# ESP12_PCB.net
KiCad netlist of a schematic drawn in Altium Designer
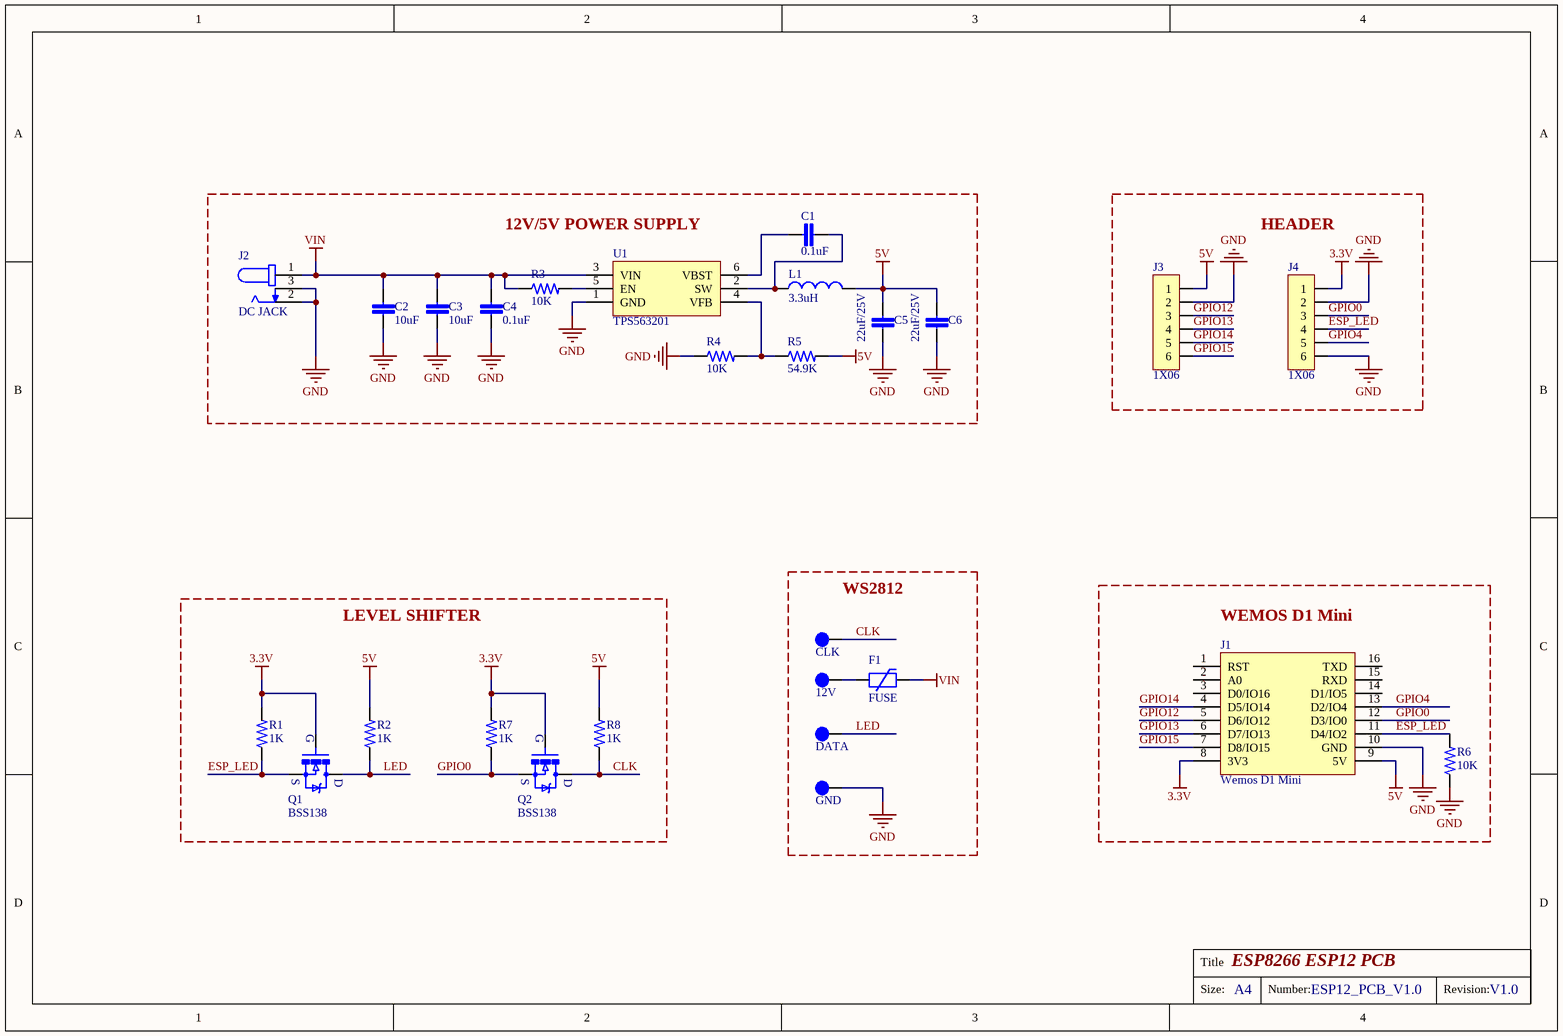
[diagram p0: ESP12_PCB.SchDoc]

(export (version "E")
  (design (tool "Eeschema 10.0.6"))
  (components
    (comp (ref "12V")
      (value "TestPoint")
      (footprint "TestPoint")
      (description "Test Point")
      (libsource (lib "Schematic_Library") (part "TestPoint"))
    )
    (comp (ref "C1")
      (value "0.1uF")
      (footprint "C1206")
      (description "0.1µF ±10% 50V Ceramic Capacitor X7R 1206 (3216 Metric)")
      (fields
        (field (name "MANUFACTURER") "Samsung")
        (field (name "MANUFACTURER PART NUMBER") "CL31B104KBCNFNC")
      )
      (libsource (lib "Schematic_Library") (part "C1206_0.1uF_50V"))
    )
    (comp (ref "C2")
      (value "10uF")
      (footprint "C1206")
      (description "10µF -20%, +80% 16V Ceramic Capacitor Y5V (F) 1206 (3216 Metric)")
      (fields
        (field (name "MANUFACTURER") "Samsung")
        (field (name "MANUFACTURER PART NUMBER") "CL31F106ZOHNNNE")
      )
      (libsource (lib "Schematic_Library") (part "C1206_10uF_16V"))
    )
    (comp (ref "C3")
      (value "10uF")
      (footprint "C1206")
      (description "10µF -20%, +80% 16V Ceramic Capacitor Y5V (F) 1206 (3216 Metric)")
      (fields
        (field (name "MANUFACTURER") "Samsung")
        (field (name "MANUFACTURER PART NUMBER") "CL31F106ZOHNNNE")
      )
      (libsource (lib "Schematic_Library") (part "C1206_10uF_16V"))
    )
    (comp (ref "C4")
      (value "0.1uF")
      (footprint "C1206")
      (description "0.1µF ±10% 50V Ceramic Capacitor X7R 1206 (3216 Metric)")
      (fields
        (field (name "MANUFACTURER") "Samsung")
        (field (name "MANUFACTURER PART NUMBER") "CL31B104KBCNFNC")
      )
      (libsource (lib "") (part "C1206_0.1uF_50V_1"))
    )
    (comp (ref "C5")
      (value "22uF/25V")
      (footprint "C1206")
      (description "Cap Ceramic 22uF 25V X5R 10% SMD 1206 85C Embossed T/R")
      (fields
        (field (name "MANUFACTURER") "Samsung")
        (field (name "MANUFACTURER PART NUMBER") "CL31A226KAHNNNE")
      )
      (libsource (lib "Schematic_Library") (part "C1206_22uF_25V"))
    )
    (comp (ref "C6")
      (value "22uF/25V")
      (footprint "C1206")
      (description "Cap Ceramic 22uF 25V X5R 10% SMD 1206 85C Embossed T/R")
      (fields
        (field (name "MANUFACTURER") "Samsung")
        (field (name "MANUFACTURER PART NUMBER") "CL31A226KAHNNNE")
      )
      (libsource (lib "Schematic_Library") (part "C1206_22uF_25V"))
    )
    (comp (ref "CLK")
      (value "TestPoint")
      (footprint "TestPoint")
      (description "Test Point")
      (libsource (lib "Schematic_Library") (part "TestPoint"))
    )
    (comp (ref "DATA")
      (value "TestPoint")
      (footprint "TestPoint")
      (description "Test Point")
      (libsource (lib "Schematic_Library") (part "TestPoint"))
    )
    (comp (ref "F1")
      (value "FUSE")
      (footprint "FUSE-SMD_L8.0-W5.4")
      (description "16V 10A 2920 PTC Resettable Fuses RoHS")
      (fields (field (name "MANUFACTURER PART NUMBER") "SMD2920P500TF/16"))
      (libsource (lib "Schematic_Library") (part "FUSE"))
    )
    (comp (ref "GND")
      (value "TestPoint")
      (footprint "TestPoint")
      (description "Test Point")
      (libsource (lib "Schematic_Library") (part "TestPoint"))
    )
    (comp (ref "J1")
      (value "Wemos D1 Mini")
      (footprint "WEMOS_D1_MINI")
      (libsource (lib "Schematic_Library") (part "Wemos_D1_Mini"))
    )
    (comp (ref "J2")
      (value "DC JACK")
      (footprint "CUI_PJ-002A")
      (description "Power Barrel Connector Jack 2.10mm ID (0.083\"), 5.50mm OD (0.217\") Through Hole, Right Angle")
      (fields (field (name "MANUFACTURER") "CUI") (field (name "MANUFACTURER PART NUMBER") "PJ-002A"))
      (libsource (lib "Schematic_Library") (part "DC_JACK_PJ-002A"))
    )
    (comp (ref "J3")
      (value "1X06")
      (footprint "CON_1X06_2.54MM_MALE")
      (description "Connector Header Through Hole 6 position 0.100\" (2.54mm)")
      (fields (field (name "MANUFACTURER PART NUMBER") "Z-211-0611-0021-001"))
      (libsource (lib "Schematic_Library") (part "CON_1X06_2.54mm_Male"))
    )
    (comp (ref "J4")
      (value "1X06")
      (footprint "CON_1X06_2.54MM_MALE")
      (description "Connector Header Through Hole 6 position 0.100\" (2.54mm)")
      (fields (field (name "MANUFACTURER PART NUMBER") "Z-211-0611-0021-001"))
      (libsource (lib "Schematic_Library") (part "CON_1X06_2.54mm_Male"))
    )
    (comp (ref "L1")
      (value "3.3uH")
      (footprint "IND_5X5")
      (description "3.3µH Shielded Wirewound Inductor 2.02A 96mOhm Max Nonstandard")
      (fields
        (field (name "MANUFACTURER") "TDK")
        (field (name "MANUFACTURER PART NUMBER") "VLCF5020T-3R3N2R0-1")
      )
      (libsource (lib "Schematic_Library") (part "INDCUTOR_3.3uH"))
    )
    (comp (ref "Q1")
      (value "BSS138")
      (footprint "SOT23-3")
      (description "N-Channel MOSFET 50V 200mA (Ta) 300mW (Ta) Surface Mount SOT-23-3")
      (fields (field (name "MANUFACTURER") "Diodes") (field (name "MANUFACTURER PART NUMBER") "BSS138-7-F"))
      (libsource (lib "Schematic_Library") (part "BSS138-7-F"))
    )
    (comp (ref "Q2")
      (value "BSS138")
      (footprint "SOT23-3")
      (description "N-Channel MOSFET 50V 200mA (Ta) 300mW (Ta) Surface Mount SOT-23-3")
      (fields (field (name "MANUFACTURER") "Diodes") (field (name "MANUFACTURER PART NUMBER") "BSS138-7-F"))
      (libsource (lib "Schematic_Library") (part "BSS138-7-F"))
    )
    (comp (ref "R1")
      (value "1K")
      (footprint "R1206")
      (fields
        (field (name "MANUFACTURER") "Yageo")
        (field (name "MANUFACTURER PART NUMBER") "AC1206FR-071KL")
        (field (name "TOLERANCE") "1%")
      )
      (libsource (lib "Schematic_Library") (part "R1206_1K"))
    )
    (comp (ref "R2")
      (value "1K")
      (footprint "R1206")
      (fields
        (field (name "MANUFACTURER") "Yageo")
        (field (name "MANUFACTURER PART NUMBER") "AC1206FR-071KL")
        (field (name "TOLERANCE") "1%")
      )
      (libsource (lib "Schematic_Library") (part "R1206_1K"))
    )
    (comp (ref "R3")
      (value "10K")
      (footprint "R1206")
      (description "10 kOhms ±5% 0.25W, 1/4W Chip Resistor 1206 (3216 Metric) Moisture Resistant Thick Film")
      (fields
        (field (name "MANUFACTURER") "Yageo")
        (field (name "MANUFACTURER PART NUMBER") "RC1206JR-0710KL")
      )
      (libsource (lib "Schematic_Library") (part "R1206_10K"))
    )
    (comp (ref "R4")
      (value "10K")
      (footprint "R1206")
      (description "10 kOhms ±5% 0.25W, 1/4W Chip Resistor 1206 (3216 Metric) Moisture Resistant Thick Film")
      (fields
        (field (name "MANUFACTURER") "Yageo")
        (field (name "MANUFACTURER PART NUMBER") "RC1206JR-0710KL")
      )
      (libsource (lib "Schematic_Library") (part "R1206_10K"))
    )
    (comp (ref "R5")
      (value "54.9K")
      (footprint "R1206")
      (description "54.9 kOhms ±1% 0.25W, 1/4W Chip Resistor 1206 (3216 Metric) Moisture Resistant Thick Film")
      (fields
        (field (name "MANUFACTURER") "Yageo")
        (field (name "MANUFACTURER PART NUMBER") "RC1206FR-0754K9L")
      )
      (libsource (lib "Schematic_Library") (part "R1206_54.9K"))
    )
    (comp (ref "R6")
      (value "10K")
      (footprint "R1206")
      (description "10 kOhms ±5% 0.25W, 1/4W Chip Resistor 1206 (3216 Metric) Moisture Resistant Thick Film")
      (fields
        (field (name "MANUFACTURER") "Yageo")
        (field (name "MANUFACTURER PART NUMBER") "RC1206JR-0710KL")
      )
      (libsource (lib "Schematic_Library") (part "R1206_10K"))
    )
    (comp (ref "R7")
      (value "1K")
      (footprint "R1206")
      (fields
        (field (name "MANUFACTURER") "Yageo")
        (field (name "MANUFACTURER PART NUMBER") "AC1206FR-071KL")
        (field (name "TOLERANCE") "1%")
      )
      (libsource (lib "Schematic_Library") (part "R1206_1K"))
    )
    (comp (ref "R8")
      (value "1K")
      (footprint "R1206")
      (fields
        (field (name "MANUFACTURER") "Yageo")
        (field (name "MANUFACTURER PART NUMBER") "AC1206FR-071KL")
        (field (name "TOLERANCE") "1%")
      )
      (libsource (lib "Schematic_Library") (part "R1206_1K"))
    )
    (comp (ref "U1")
      (value "TPS563201")
      (footprint "SOT23-6")
      (description "Conv DC-DC 4.5V to 17V Synchronous Step Down Single-Out 0.76V to 7V 3A 6-Pin TSOT-23 T/R")
      (fields
        (field (name "MANUFACTURER") "Texas Instruments")
        (field (name "MANUFACTURER PART NUMBER") "TPS563201DDCR")
      )
      (libsource (lib "Schematic_Library") (part "TPS563201DDCR"))
    )
  )
  (nets
    (net (code "1") (name "/CLK") (class "Default")
      (node (ref "CLK") (pin "1") (pinfunction "1_1") (pintype "passive"))
      (node (ref "Q2") (pin "3") (pinfunction "D_3") (pintype "passive"))
      (node (ref "R8") (pin "1") (pinfunction "1_1") (pintype "passive"))
    )
    (net (code "2") (name "/ESP_LED") (class "Default")
      (node (ref "J1") (pin "11") (pinfunction "D4/IO2_11") (pintype "passive"))
      (node (ref "J4") (pin "4") (pinfunction "4_4") (pintype "passive"))
      (node (ref "Q1") (pin "2") (pinfunction "S_2") (pintype "passive"))
      (node (ref "R1") (pin "1") (pinfunction "1_1") (pintype "passive"))
      (node (ref "R6") (pin "2") (pinfunction "2_2") (pintype "passive"))
    )
    (net (code "3") (name "/GPIO0") (class "Default")
      (node (ref "J1") (pin "12") (pinfunction "D3/IO0_12") (pintype "passive"))
      (node (ref "J4") (pin "3") (pinfunction "3_3") (pintype "passive"))
      (node (ref "Q2") (pin "2") (pinfunction "S_2") (pintype "passive"))
      (node (ref "R7") (pin "1") (pinfunction "1_1") (pintype "passive"))
    )
    (net (code "4") (name "/GPIO4") (class "Default")
      (node (ref "J1") (pin "13") (pinfunction "D2/IO4_13") (pintype "passive"))
      (node (ref "J4") (pin "5") (pinfunction "5_5") (pintype "passive"))
    )
    (net (code "5") (name "/GPIO12") (class "Default")
      (node (ref "J1") (pin "5") (pinfunction "D6/IO12_5") (pintype "passive"))
      (node (ref "J3") (pin "3") (pinfunction "3_3") (pintype "passive"))
    )
    (net (code "6") (name "/GPIO13") (class "Default")
      (node (ref "J1") (pin "6") (pinfunction "D7/IO13_6") (pintype "passive"))
      (node (ref "J3") (pin "4") (pinfunction "4_4") (pintype "passive"))
    )
    (net (code "7") (name "/GPIO14") (class "Default")
      (node (ref "J1") (pin "4") (pinfunction "D5/IO14_4") (pintype "passive"))
      (node (ref "J3") (pin "5") (pinfunction "5_5") (pintype "passive"))
    )
    (net (code "8") (name "/GPIO15") (class "Default")
      (node (ref "J1") (pin "7") (pinfunction "D8/IO15_7") (pintype "passive"))
      (node (ref "J3") (pin "6") (pinfunction "6_6") (pintype "passive"))
    )
    (net (code "9") (name "/LED") (class "Default")
      (node (ref "DATA") (pin "1") (pinfunction "1_1") (pintype "passive"))
      (node (ref "Q1") (pin "3") (pinfunction "D_3") (pintype "passive"))
      (node (ref "R2") (pin "1") (pinfunction "1_1") (pintype "passive"))
    )
    (net (code "10") (name "3.3V") (class "Default")
      (node (ref "J1") (pin "8") (pinfunction "3V3_8") (pintype "passive"))
      (node (ref "J4") (pin "1") (pinfunction "1_1") (pintype "passive"))
      (node (ref "Q1") (pin "1") (pinfunction "G_1") (pintype "passive"))
      (node (ref "Q2") (pin "1") (pinfunction "G_1") (pintype "passive"))
      (node (ref "R1") (pin "2") (pinfunction "2_2") (pintype "passive"))
      (node (ref "R7") (pin "2") (pinfunction "2_2") (pintype "passive"))
    )
    (net (code "11") (name "5V") (class "Default")
      (node (ref "C5") (pin "1") (pinfunction "1_1") (pintype "passive"))
      (node (ref "C6") (pin "1") (pinfunction "1_1") (pintype "passive"))
      (node (ref "J1") (pin "9") (pinfunction "5V_9") (pintype "passive"))
      (node (ref "J3") (pin "1") (pinfunction "1_1") (pintype "passive"))
      (node (ref "L1") (pin "2") (pinfunction "2_2") (pintype "passive"))
      (node (ref "R2") (pin "2") (pinfunction "2_2") (pintype "passive"))
      (node (ref "R5") (pin "2") (pinfunction "2_2") (pintype "passive"))
      (node (ref "R8") (pin "2") (pinfunction "2_2") (pintype "passive"))
    )
    (net (code "12") (name "GND") (class "Default")
      (node (ref "C2") (pin "2") (pinfunction "2_2") (pintype "passive"))
      (node (ref "C3") (pin "2") (pinfunction "2_2") (pintype "passive"))
      (node (ref "C4") (pin "2") (pinfunction "2_2") (pintype "passive"))
      (node (ref "C5") (pin "2") (pinfunction "2_2") (pintype "passive"))
      (node (ref "C6") (pin "2") (pinfunction "2_2") (pintype "passive"))
      (node (ref "GND") (pin "1") (pinfunction "1_1") (pintype "passive"))
      (node (ref "J1") (pin "10") (pinfunction "GND_10") (pintype "passive"))
      (node (ref "J2") (pin "2") (pinfunction "2_2") (pintype "passive"))
      (node (ref "J2") (pin "3") (pinfunction "3_3") (pintype "passive"))
      (node (ref "J3") (pin "2") (pinfunction "2_2") (pintype "passive"))
      (node (ref "J4") (pin "2") (pinfunction "2_2") (pintype "passive"))
      (node (ref "J4") (pin "6") (pinfunction "6_6") (pintype "passive"))
      (node (ref "R4") (pin "1") (pinfunction "1_1") (pintype "passive"))
      (node (ref "R6") (pin "1") (pinfunction "1_1") (pintype "passive"))
      (node (ref "U1") (pin "1") (pinfunction "GND_1") (pintype "passive"))
    )
    (net (code "13") (name "Net-(12V-Pad1)") (class "Default")
      (node (ref "12V") (pin "1") (pinfunction "1_1") (pintype "passive"))
      (node (ref "F1") (pin "1") (pinfunction "1_1") (pintype "passive"))
    )
    (net (code "14") (name "Net-(U1-EN)") (class "Default")
      (node (ref "R3") (pin "2") (pinfunction "2_2") (pintype "passive"))
      (node (ref "U1") (pin "5") (pinfunction "EN_5") (pintype "passive"))
    )
    (net (code "15") (name "Net-(U1-SW)") (class "Default")
      (node (ref "C1") (pin "2") (pinfunction "2_2") (pintype "passive"))
      (node (ref "L1") (pin "1") (pinfunction "1_1") (pintype "passive"))
      (node (ref "U1") (pin "2") (pinfunction "SW_2") (pintype "passive"))
    )
    (net (code "16") (name "Net-(U1-VBST)") (class "Default")
      (node (ref "C1") (pin "1") (pinfunction "1_1") (pintype "passive"))
      (node (ref "U1") (pin "6") (pinfunction "VBST_6") (pintype "passive"))
    )
    (net (code "17") (name "Net-(U1-VFB)") (class "Default")
      (node (ref "R4") (pin "2") (pinfunction "2_2") (pintype "passive"))
      (node (ref "R5") (pin "1") (pinfunction "1_1") (pintype "passive"))
      (node (ref "U1") (pin "4") (pinfunction "VFB_4") (pintype "passive"))
    )
    (net (code "18") (name "VIN") (class "Default")
      (node (ref "C2") (pin "1") (pinfunction "1_1") (pintype "passive"))
      (node (ref "C3") (pin "1") (pinfunction "1_1") (pintype "passive"))
      (node (ref "C4") (pin "1") (pinfunction "1_1") (pintype "passive"))
      (node (ref "F1") (pin "2") (pinfunction "2_2") (pintype "passive"))
      (node (ref "J2") (pin "1") (pinfunction "1_1") (pintype "passive"))
      (node (ref "R3") (pin "1") (pinfunction "1_1") (pintype "passive"))
      (node (ref "U1") (pin "3") (pinfunction "VIN_3") (pintype "passive"))
    )
    (net (code "19") (name "unconnected-(J1-A0-Pad2)") (class "Default")
      (node (ref "J1") (pin "2") (pinfunction "A0_2") (pintype "passive"))
    )
    (net (code "20") (name "unconnected-(J1-D0{slash}IO16-Pad3)") (class "Default")
      (node (ref "J1") (pin "3") (pinfunction "D0/IO16_3") (pintype "passive"))
    )
    (net (code "21") (name "unconnected-(J1-D1{slash}IO5-Pad14)") (class "Default")
      (node (ref "J1") (pin "14") (pinfunction "D1/IO5_14") (pintype "passive"))
    )
    (net (code "22") (name "unconnected-(J1-RST-Pad1)") (class "Default")
      (node (ref "J1") (pin "1") (pinfunction "RST_1") (pintype "passive"))
    )
    (net (code "23") (name "unconnected-(J1-RXD-Pad15)") (class "Default")
      (node (ref "J1") (pin "15") (pinfunction "RXD_15") (pintype "passive"))
    )
    (net (code "24") (name "unconnected-(J1-TXD-Pad16)") (class "Default")
      (node (ref "J1") (pin "16") (pinfunction "TXD_16") (pintype "passive"))
    )
  )
)
